# 24_PCIE-PCIE3_0_1x4Lanes_RC_64P.net
KiCad netlist of a schematic drawn in Altium Designer
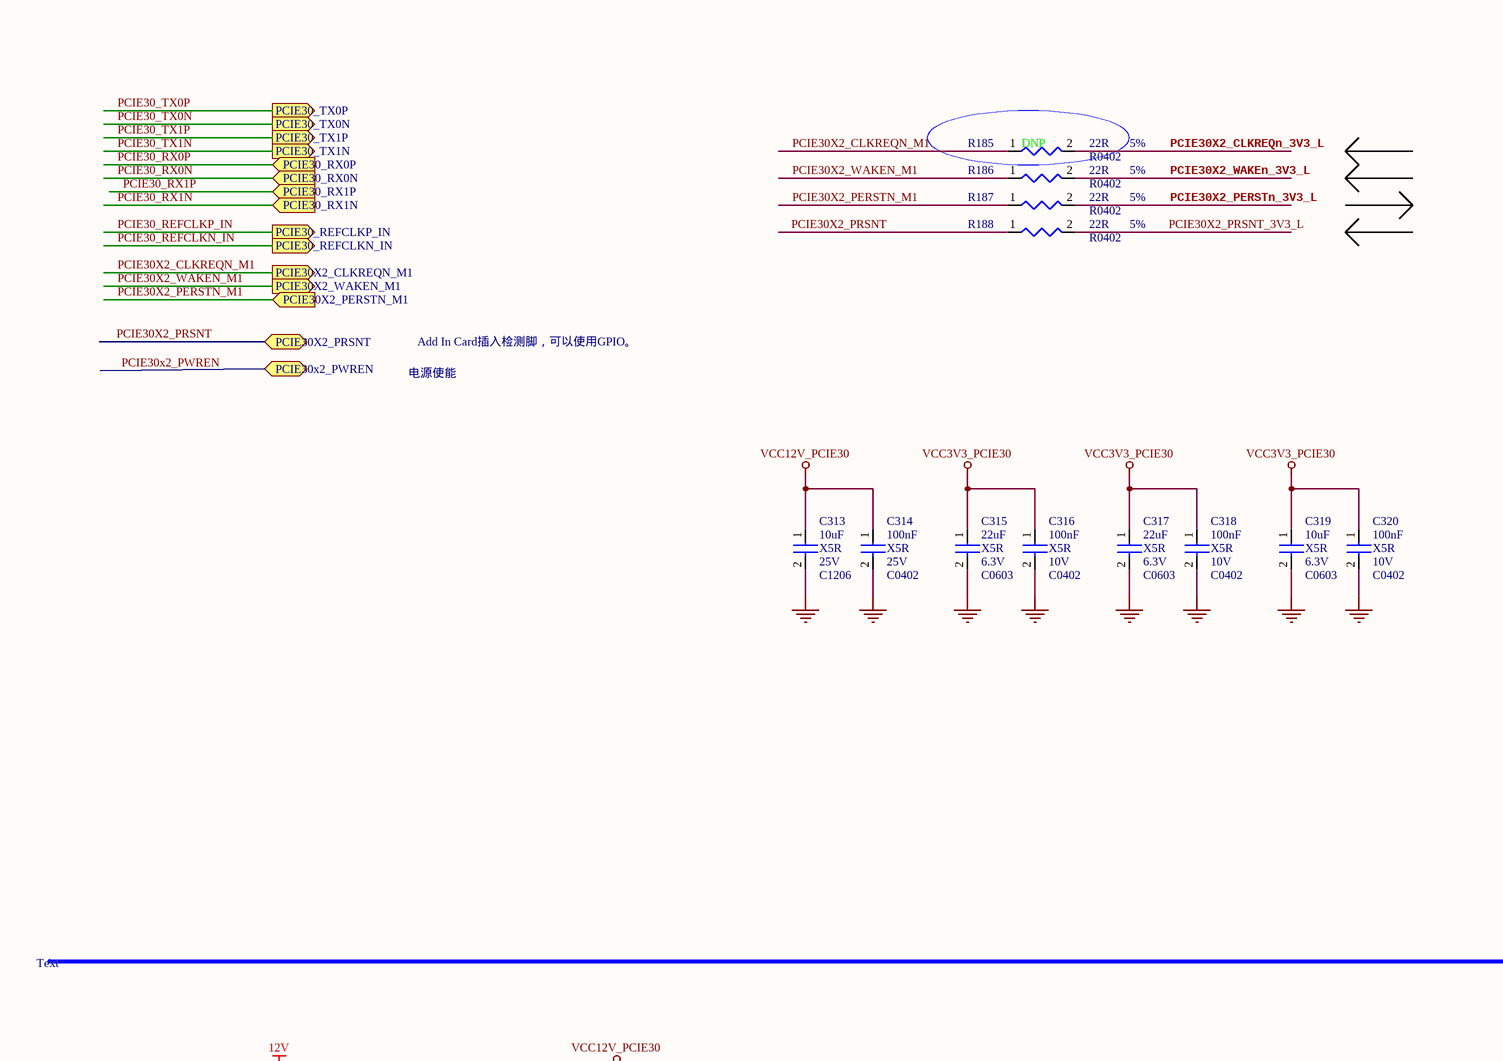
[diagram p0: 24_PCIE-PCIE3.0_1x4Lanes_RC_64P.SchDoc, top left]
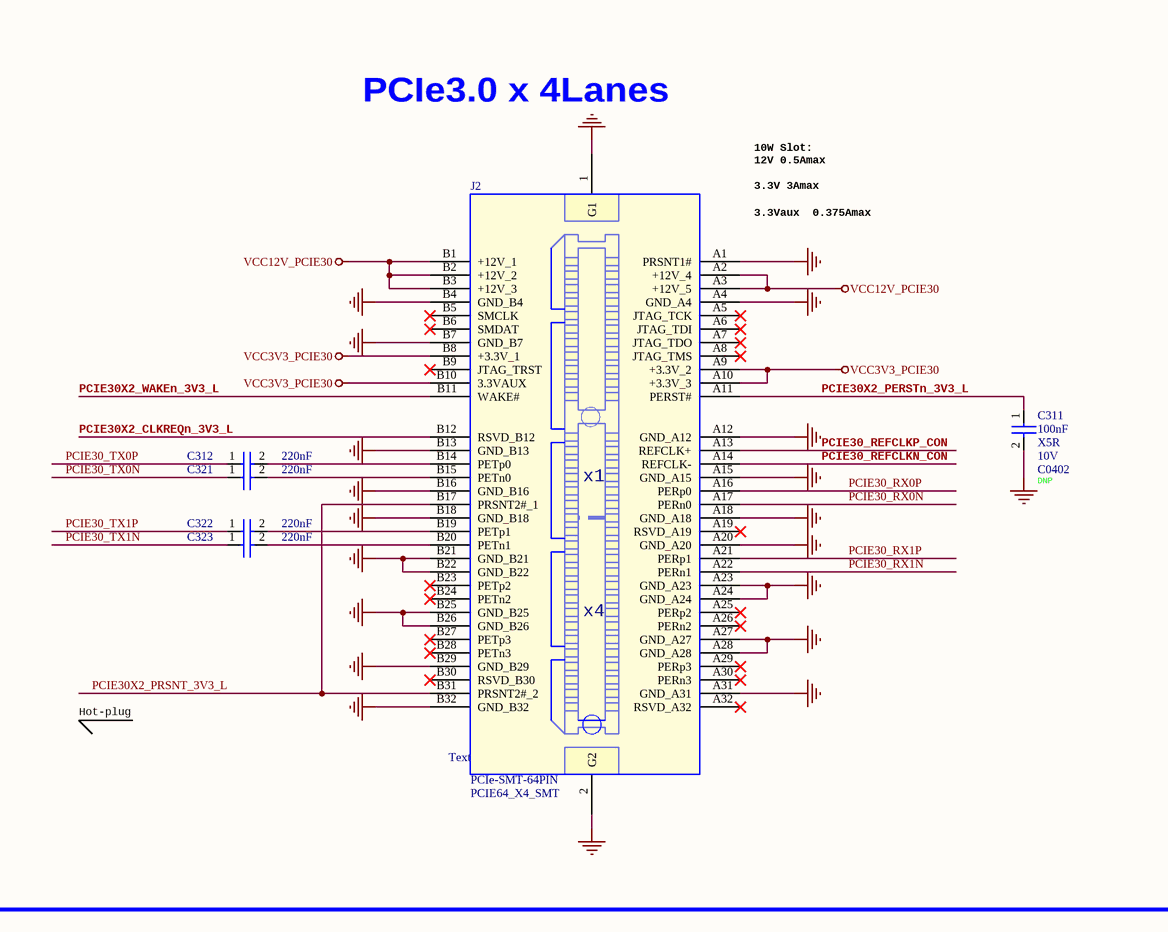
[diagram p1: 24_PCIE-PCIE3.0_1x4Lanes_RC_64P.SchDoc, top right]
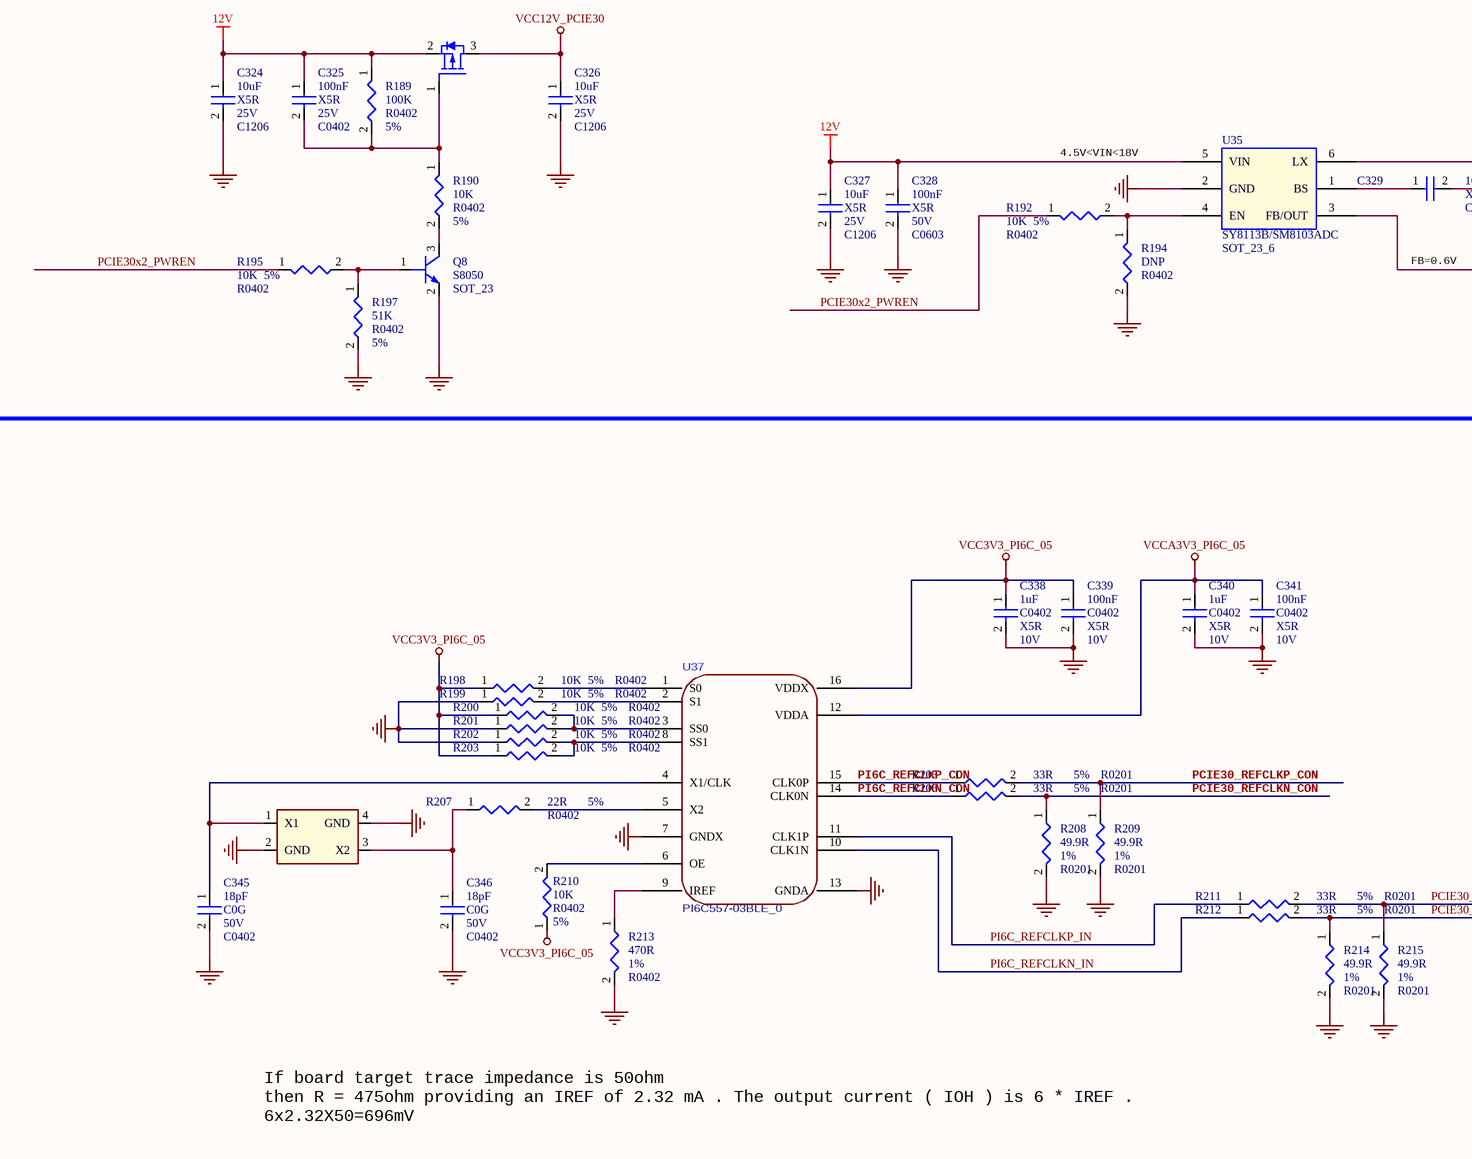
[diagram p2: 24_PCIE-PCIE3.0_1x4Lanes_RC_64P.SchDoc, bottom left]
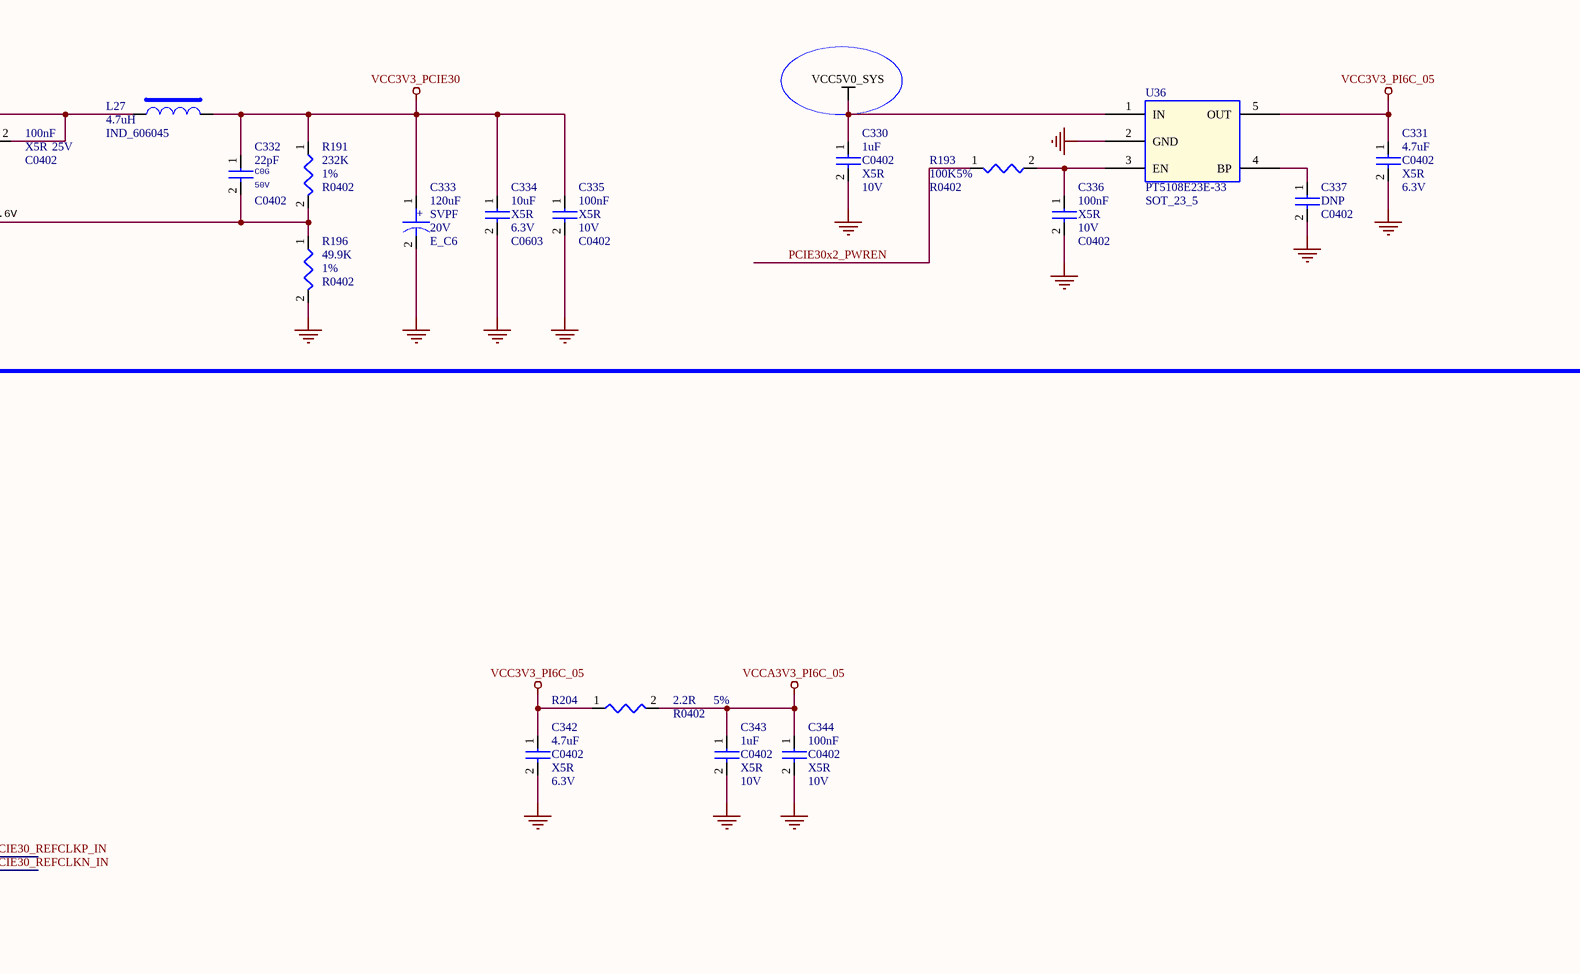
[diagram p3: 24_PCIE-PCIE3.0_1x4Lanes_RC_64P.SchDoc, bottom right]

(export (version "E")
  (design (tool "Eeschema 10.0.6"))
  (components
    (comp (ref "C311")
      (value "100nF")
      (footprint "C0402")
      (description "cap,100.00nF,+/-10%,10V,X5R,C0402")
      (fields
        (field (name "VOLTAGE") "10V")
        (field (name "PCB FOOTPRINT") "C0402")
        (field (name "DIELECTRIC") "X5R")
        (field (name "TOLERANCE") "10%")
        (field (name "MANUFACTURER") "TDK")
        (field (name "OPTION") "DNP")
        (field (name "CREATED BY") "JJJ")
      )
      (libsource (lib "*") (part "CAP NP"))
    )
    (comp (ref "C312")
      (value "220nF")
      (footprint "C0201")
      (description "cap,220.00nF,+/-10%,10V,X5R,C0201")
      (fields
        (field (name "MANUFACTURER") "TDK")
        (field (name "TOLERANCE") "10%")
        (field (name "CREATED BY") "JJJ")
      )
      (libsource (lib "*") (part "CAP NP"))
    )
    (comp (ref "C313")
      (value "10uF")
      (footprint "C1206")
      (description "cap,10.00uF,+/-10%,25V,X5R,C1206")
      (fields
        (field (name "VOLTAGE") "25V")
        (field (name "PCB FOOTPRINT") "C1206")
        (field (name "DIELECTRIC") "X5R")
        (field (name "MANUFACTURER") "TDK")
        (field (name "TOLERANCE") "10%")
        (field (name "CREATED BY") "JJJ")
      )
      (libsource (lib "*") (part "CAP NP"))
    )
    (comp (ref "C314")
      (value "100nF")
      (footprint "C0402")
      (description "cap,100.00nF,+/-10%,25V,X5R,C0402")
      (fields
        (field (name "VOLTAGE") "25V")
        (field (name "PCB FOOTPRINT") "C0402")
        (field (name "DIELECTRIC") "X5R")
        (field (name "TOLERANCE") "10%")
        (field (name "MANUFACTURER") "TDK")
        (field (name "CREATED BY") "JJJ")
      )
      (libsource (lib "*") (part "CAP NP"))
    )
    (comp (ref "C315")
      (value "22uF")
      (footprint "C0603")
      (description "cap,22.00uF,+/-20%,6.3V,X5R,C0603")
      (fields
        (field (name "VOLTAGE") "6.3V")
        (field (name "PCB FOOTPRINT") "C0603")
        (field (name "DIELECTRIC") "X5R")
        (field (name "MANUFACTURER") "TDK")
        (field (name "TOLERANCE") "20%")
        (field (name "CREATED BY") "JJJ")
      )
      (libsource (lib "*") (part "CAP NP"))
    )
    (comp (ref "C316")
      (value "100nF")
      (footprint "C0402")
      (description "cap,100.00nF,+/-10%,10V,X5R,C0402")
      (fields
        (field (name "VOLTAGE") "10V")
        (field (name "PCB FOOTPRINT") "C0402")
        (field (name "DIELECTRIC") "X5R")
        (field (name "MANUFACTURER") "TDK")
        (field (name "TOLERANCE") "10%")
        (field (name "CREATED BY") "JJJ")
      )
      (libsource (lib "*") (part "CAP NP"))
    )
    (comp (ref "C317")
      (value "22uF")
      (footprint "C0603")
      (description "cap,22.00uF,+/-20%,6.3V,X5R,C0603")
      (fields
        (field (name "VOLTAGE") "6.3V")
        (field (name "PCB FOOTPRINT") "C0603")
        (field (name "DIELECTRIC") "X5R")
        (field (name "MANUFACTURER") "TDK")
        (field (name "TOLERANCE") "20%")
        (field (name "CREATED BY") "JJJ")
      )
      (libsource (lib "*") (part "CAP NP"))
    )
    (comp (ref "C318")
      (value "100nF")
      (footprint "C0402")
      (description "cap,100.00nF,+/-10%,10V,X5R,C0402")
      (fields
        (field (name "VOLTAGE") "10V")
        (field (name "PCB FOOTPRINT") "C0402")
        (field (name "DIELECTRIC") "X5R")
        (field (name "MANUFACTURER") "TDK")
        (field (name "TOLERANCE") "10%")
        (field (name "CREATED BY") "JJJ")
      )
      (libsource (lib "*") (part "CAP NP"))
    )
    (comp (ref "C319")
      (value "10uF")
      (footprint "C0603")
      (description "cap,10.00uF,+/-10%,6.3V,X5R,C0603")
      (fields
        (field (name "VOLTAGE") "6.3V")
        (field (name "PCB FOOTPRINT") "C0603")
        (field (name "DIELECTRIC") "X5R")
        (field (name "TOLERANCE") "10%")
        (field (name "MANUFACTURER") "TDK")
        (field (name "CREATED BY") "JJJ")
      )
      (libsource (lib "*") (part "CAP NP"))
    )
    (comp (ref "C320")
      (value "100nF")
      (footprint "C0402")
      (description "cap,100.00nF,+/-10%,10V,X5R,C0402")
      (fields
        (field (name "VOLTAGE") "10V")
        (field (name "PCB FOOTPRINT") "C0402")
        (field (name "DIELECTRIC") "X5R")
        (field (name "TOLERANCE") "10%")
        (field (name "MANUFACTURER") "TDK")
        (field (name "CREATED BY") "JJJ")
      )
      (libsource (lib "*") (part "CAP NP"))
    )
    (comp (ref "C321")
      (value "220nF")
      (footprint "C0201")
      (description "cap,220.00nF,+/-10%,10V,X5R,C0201")
      (fields
        (field (name "MANUFACTURER") "TDK")
        (field (name "TOLERANCE") "10%")
        (field (name "CREATED BY") "JJJ")
      )
      (libsource (lib "*") (part "CAP NP"))
    )
    (comp (ref "C322")
      (value "220nF")
      (footprint "C0201")
      (description "cap,220.00nF,+/-10%,10V,X5R,C0201")
      (fields
        (field (name "MANUFACTURER") "TDK")
        (field (name "TOLERANCE") "10%")
        (field (name "CREATED BY") "JJJ")
      )
      (libsource (lib "*") (part "CAP NP"))
    )
    (comp (ref "C323")
      (value "220nF")
      (footprint "C0201")
      (description "cap,220.00nF,+/-10%,10V,X5R,C0201")
      (fields
        (field (name "MANUFACTURER") "TDK")
        (field (name "TOLERANCE") "10%")
        (field (name "CREATED BY") "JJJ")
      )
      (libsource (lib "*") (part "CAP NP"))
    )
    (comp (ref "C324")
      (value "10uF")
      (footprint "C1206")
      (description "cap,10.00uF,+/-10%,25V,X5R,C1206")
      (fields
        (field (name "VOLTAGE") "25V")
        (field (name "PCB FOOTPRINT") "C1206")
        (field (name "DIELECTRIC") "X5R")
        (field (name "TOLERANCE") "10%")
        (field (name "MANUFACTURER") "TDK")
        (field (name "CREATED BY") "JJJ")
      )
      (libsource (lib "*") (part "CAP NP"))
    )
    (comp (ref "C325")
      (value "100nF")
      (footprint "C0402")
      (description "cap,100.00nF,+/-10%,25V,X5R,C0402")
      (fields
        (field (name "VOLTAGE") "25V")
        (field (name "PCB FOOTPRINT") "C0402")
        (field (name "DIELECTRIC") "X5R")
        (field (name "MANUFACTURER") "TDK")
        (field (name "TOLERANCE") "10%")
        (field (name "CREATED BY") "JJJ")
      )
      (libsource (lib "*") (part "CAP NP"))
    )
    (comp (ref "C326")
      (value "10uF")
      (footprint "C1206")
      (description "cap,10.00uF,+/-10%,25V,X5R,C1206")
      (fields
        (field (name "VOLTAGE") "25V")
        (field (name "PCB FOOTPRINT") "C1206")
        (field (name "DIELECTRIC") "X5R")
        (field (name "TOLERANCE") "10%")
        (field (name "MANUFACTURER") "TDK")
        (field (name "CREATED BY") "JJJ")
      )
      (libsource (lib "*") (part "CAP NP"))
    )
    (comp (ref "C327")
      (value "10uF")
      (footprint "C1206")
      (description "cap,10.00uF,+/-10%,25V,X5R,C1206")
      (fields
        (field (name "VOLTAGE") "25V")
        (field (name "PCB FOOTPRINT") "C1206")
        (field (name "DIELECTRIC") "X5R")
        (field (name "MANUFACTURER") "TDK")
        (field (name "TOLERANCE") "10%")
        (field (name "CREATED BY") "JJJ")
      )
      (libsource (lib "*") (part "CAP NP"))
    )
    (comp (ref "C328")
      (value "100nF")
      (footprint "C0603")
      (description "cap,100.00nF,+/-10%,50V,X5R,C0603")
      (fields
        (field (name "VOLTAGE") "50V")
        (field (name "PCB FOOTPRINT") "C0603")
        (field (name "DIELECTRIC") "X5R")
        (field (name "MANUFACTURER") "TDK")
        (field (name "TOLERANCE") "10%")
        (field (name "CREATED BY") "JJJ")
      )
      (libsource (lib "*") (part "CAP NP"))
    )
    (comp (ref "C329")
      (value "100nF")
      (footprint "C0402")
      (description "cap,100.00nF,+/-10%,25V,X5R,C0402")
      (fields
        (field (name "VOLTAGE") "25V")
        (field (name "PCB FOOTPRINT") "C0402")
        (field (name "DIELECTRIC") "X5R")
        (field (name "TOLERANCE") "10%")
        (field (name "MANUFACTURER") "TDK")
        (field (name "CREATED BY") "JJJ")
      )
      (libsource (lib "*") (part "CAP NP"))
    )
    (comp (ref "C330")
      (value "1uF")
      (footprint "C0402")
      (description "cap,1.00uF,+/-10%,10V,X5R,C0402")
      (fields
        (field (name "VOLTAGE") "10V")
        (field (name "PCB FOOTPRINT") "C0402")
        (field (name "DIELECTRIC") "X5R")
        (field (name "TOLERANCE") "10%")
        (field (name "MANUFACTURER") "TDK")
        (field (name "CREATED BY") "JJJ")
      )
      (libsource (lib "*") (part "CAP NP"))
    )
    (comp (ref "C331")
      (value "4.7uF")
      (footprint "C0402")
      (description "cap,4.70uF,+/-10%,6.3V,X5R,C0402")
      (fields
        (field (name "VOLTAGE") "6.3V")
        (field (name "PCB FOOTPRINT") "C0402")
        (field (name "DIELECTRIC") "X5R")
        (field (name "MANUFACTURER") "TDK")
        (field (name "TOLERANCE") "10%")
        (field (name "CREATED BY") "JJJ")
      )
      (libsource (lib "*") (part "CAP NP"))
    )
    (comp (ref "C332")
      (value "22pF")
      (footprint "C0402")
      (description "cap,22.00pF,+/-5%,50V,C0G,C0402")
      (fields
        (field (name "VOLTAGE") "50V")
        (field (name "PCB FOOTPRINT") "C0402")
        (field (name "DIELECTRIC") "C0G")
        (field (name "TOLERANCE") "5%")
        (field (name "MANUFACTURER") "TDK")
        (field (name "CREATED BY") "JJJ")
      )
      (libsource (lib "*") (part "CAP NP"))
    )
    (comp (ref "C333")
      (value "120uF")
      (footprint "E_C6")
      (description "120uF,20V,25mR,SVPF")
      (fields
        (field (name "VOLTAGE") "20V")
        (field (name "DIELECTRIC") "SVPF")
        (field (name "PCB FOOTPRINT") "E_C6")
        (field (name "MANUFACTURER") "Panasonic")
        (field (name "TOLERANCE") "20%")
        (field (name "CREATED BY") "JJJ")
      )
      (libsource (lib "*") (part "CAP"))
    )
    (comp (ref "C334")
      (value "10uF")
      (footprint "C0603")
      (description "cap,10.00uF,+/-10%,6.3V,X5R,C0603")
      (fields
        (field (name "VOLTAGE") "6.3V")
        (field (name "PCB FOOTPRINT") "C0603")
        (field (name "DIELECTRIC") "X5R")
        (field (name "TOLERANCE") "10%")
        (field (name "MANUFACTURER") "TDK")
        (field (name "CREATED BY") "JJJ")
      )
      (libsource (lib "*") (part "CAP NP"))
    )
    (comp (ref "C335")
      (value "100nF")
      (footprint "C0402")
      (description "cap,100.00nF,+/-10%,10V,X5R,C0402")
      (fields
        (field (name "VOLTAGE") "10V")
        (field (name "PCB FOOTPRINT") "C0402")
        (field (name "DIELECTRIC") "X5R")
        (field (name "MANUFACTURER") "TDK")
        (field (name "TOLERANCE") "10%")
        (field (name "CREATED BY") "JJJ")
      )
      (libsource (lib "*") (part "CAP NP"))
    )
    (comp (ref "C336")
      (value "100nF")
      (footprint "C0402")
      (description "cap,100.00nF,+/-10%,10V,X5R,C0402")
      (fields
        (field (name "VOLTAGE") "10V")
        (field (name "PCB FOOTPRINT") "C0402")
        (field (name "DIELECTRIC") "X5R")
        (field (name "TOLERANCE") "10%")
        (field (name "MANUFACTURER") "TDK")
        (field (name "CREATED BY") "JJJ")
      )
      (libsource (lib "*") (part "CAP NP"))
    )
    (comp (ref "C337")
      (value "DNP")
      (footprint "C0402")
      (description "Did Not Place.")
      (fields (field (name "PCB FOOTPRINT") "C0402") (field (name "CREATED BY") "JJJ"))
      (libsource (lib "*") (part "CAP NP"))
    )
    (comp (ref "C338")
      (value "1uF")
      (footprint "C0402")
      (description "cap,1.00uF,+/-10%,10V,X5R,C0402")
      (fields
        (field (name "VOLTAGE") "10V")
        (field (name "PCB FOOTPRINT") "C0402")
        (field (name "DIELECTRIC") "X5R")
        (field (name "MANUFACTURER") "TDK")
        (field (name "TOLERANCE") "10%")
        (field (name "CREATED BY") "JJJ")
      )
      (libsource (lib "*") (part "CAP NP"))
    )
    (comp (ref "C339")
      (value "100nF")
      (footprint "C0402")
      (description "cap,100.00nF,+/-10%,10V,X5R,C0402")
      (fields
        (field (name "VOLTAGE") "10V")
        (field (name "PCB FOOTPRINT") "C0402")
        (field (name "DIELECTRIC") "X5R")
        (field (name "TOLERANCE") "10%")
        (field (name "MANUFACTURER") "TDK")
        (field (name "CREATED BY") "JJJ")
      )
      (libsource (lib "*") (part "CAP NP"))
    )
    (comp (ref "C340")
      (value "1uF")
      (footprint "C0402")
      (description "cap,1.00uF,+/-10%,10V,X5R,C0402")
      (fields
        (field (name "VOLTAGE") "10V")
        (field (name "PCB FOOTPRINT") "C0402")
        (field (name "DIELECTRIC") "X5R")
        (field (name "MANUFACTURER") "TDK")
        (field (name "TOLERANCE") "10%")
        (field (name "CREATED BY") "JJJ")
      )
      (libsource (lib "*") (part "CAP NP"))
    )
    (comp (ref "C341")
      (value "100nF")
      (footprint "C0402")
      (description "cap,100.00nF,+/-10%,10V,X5R,C0402")
      (fields
        (field (name "VOLTAGE") "10V")
        (field (name "PCB FOOTPRINT") "C0402")
        (field (name "DIELECTRIC") "X5R")
        (field (name "TOLERANCE") "10%")
        (field (name "MANUFACTURER") "TDK")
        (field (name "CREATED BY") "JJJ")
      )
      (libsource (lib "*") (part "CAP NP"))
    )
    (comp (ref "C342")
      (value "4.7uF")
      (footprint "C0402")
      (description "cap,4.70uF,+/-10%,6.3V,X5R,C0402")
      (fields
        (field (name "VOLTAGE") "6.3V")
        (field (name "PCB FOOTPRINT") "C0402")
        (field (name "DIELECTRIC") "X5R")
        (field (name "TOLERANCE") "10%")
        (field (name "MANUFACTURER") "TDK")
        (field (name "CREATED BY") "JJJ")
      )
      (libsource (lib "*") (part "CAP NP"))
    )
    (comp (ref "C343")
      (value "1uF")
      (footprint "C0402")
      (description "cap,1.00uF,+/-10%,10V,X5R,C0402")
      (fields
        (field (name "VOLTAGE") "10V")
        (field (name "PCB FOOTPRINT") "C0402")
        (field (name "DIELECTRIC") "X5R")
        (field (name "MANUFACTURER") "TDK")
        (field (name "TOLERANCE") "10%")
        (field (name "CREATED BY") "JJJ")
      )
      (libsource (lib "*") (part "CAP NP"))
    )
    (comp (ref "C344")
      (value "100nF")
      (footprint "C0402")
      (description "cap,100.00nF,+/-10%,10V,X5R,C0402")
      (fields
        (field (name "VOLTAGE") "10V")
        (field (name "PCB FOOTPRINT") "C0402")
        (field (name "DIELECTRIC") "X5R")
        (field (name "TOLERANCE") "10%")
        (field (name "MANUFACTURER") "TDK")
        (field (name "CREATED BY") "JJJ")
      )
      (libsource (lib "*") (part "CAP NP"))
    )
    (comp (ref "C345")
      (value "18pF")
      (footprint "C0402")
      (description "cap,18.00pF,+/-5%,50V,C0G,C0402")
      (fields
        (field (name "VOLTAGE") "50V")
        (field (name "PCB FOOTPRINT") "C0402")
        (field (name "DIELECTRIC") "C0G")
        (field (name "TOLERANCE") "5%")
        (field (name "MANUFACTURER") "TDK")
        (field (name "CREATED BY") "JJJ")
      )
      (libsource (lib "*") (part "CAP NP"))
    )
    (comp (ref "C346")
      (value "18pF")
      (footprint "C0402")
      (description "cap,18.00pF,+/-5%,50V,C0G,C0402")
      (fields
        (field (name "VOLTAGE") "50V")
        (field (name "PCB FOOTPRINT") "C0402")
        (field (name "DIELECTRIC") "C0G")
        (field (name "MANUFACTURER") "TDK")
        (field (name "TOLERANCE") "5%")
        (field (name "CREATED BY") "JJJ")
      )
      (libsource (lib "*") (part "CAP NP"))
    )
    (comp (ref "J2")
      (value "PCIe-SMT-64PIN")
      (footprint "PCIE64_X4_SMT")
      (fields (field (name "PCB FOOTPRINT") "PCIE64_X4_SMT"))
      (libsource (lib "*") (part "PCIeX4_1"))
    )
    (comp (ref "L27")
      (value "4.7uH")
      (footprint "IND_606045")
      (description "Power Inductor,4.7uH,0.2,IND_606045")
      (fields
        (field (name "PCB FOOTPRINT") "IND_606045")
        (field (name "MANUFACTURER") "sunlord")
        (field (name "TOLERANCE") "20%")
        (field (name "CREATED BY") "YWQ")
      )
      (libsource (lib "*") (part "INDUCTORS OF FERRITE_Dup1"))
    )
    (comp (ref "Q7") (value "MOSFET P") (footprint "SOT_23") (libsource (lib "RK3568核心板") (part "MOSFET P")))
    (comp (ref "Q8")
      (value "S8050")
      (footprint "SOT_23")
      (description "S8050,SOT23")
      (fields
        (field (name "PCB FOOTPRINT") "SOT_23")
        (field (name "MANUFACTURER") "长电")
        (field (name "CREATED BY") "JJJ")
      )
      (libsource (lib "*") (part "NPN"))
    )
    (comp (ref "R185")
      (value "22R")
      (footprint "R0402")
      (description "通用厚膜电阻,22R,+/-5%,R0402,1/16W.")
      (fields
        (field (name "PCB FOOTPRINT") "R0402")
        (field (name "TOLERANCE") "5%")
        (field (name "MANUFACTURER") "YAGEO")
        (field (name "OPTION") "DNP")
        (field (name "CREATED BY") "YTL")
      )
      (libsource (lib "*") (part "RESISTOR_Dup1"))
    )
    (comp (ref "R186")
      (value "22R")
      (footprint "R0402")
      (description "通用厚膜电阻,22R,+/-5%,R0402,1/16W.")
      (fields
        (field (name "PCB FOOTPRINT") "R0402")
        (field (name "TOLERANCE") "5%")
        (field (name "MANUFACTURER") "YAGEO")
        (field (name "CREATED BY") "YTL")
      )
      (libsource (lib "*") (part "RESISTOR_Dup1"))
    )
    (comp (ref "R187")
      (value "22R")
      (footprint "R0402")
      (description "通用厚膜电阻,22R,+/-5%,R0402,1/16W.")
      (fields
        (field (name "PCB FOOTPRINT") "R0402")
        (field (name "TOLERANCE") "5%")
        (field (name "MANUFACTURER") "YAGEO")
        (field (name "CREATED BY") "YTL")
      )
      (libsource (lib "*") (part "RESISTOR_Dup1"))
    )
    (comp (ref "R188")
      (value "22R")
      (footprint "R0402")
      (description "通用厚膜电阻,22R,+/-5%,R0402,1/16W.")
      (fields
        (field (name "PCB FOOTPRINT") "R0402")
        (field (name "TOLERANCE") "5%")
        (field (name "MANUFACTURER") "YAGEO")
        (field (name "CREATED BY") "YTL")
      )
      (libsource (lib "*") (part "RESISTOR_Dup1"))
    )
    (comp (ref "R189")
      (value "100K")
      (footprint "R0402")
      (description "通用厚膜电阻,100K,+/-5%,R0402,1/16W.")
      (fields
        (field (name "PCB FOOTPRINT") "R0402")
        (field (name "TOLERANCE") "5%")
        (field (name "MANUFACTURER") "YAGEO")
        (field (name "CREATED BY") "YTL")
      )
      (libsource (lib "*") (part "RESISTOR_Dup1"))
    )
    (comp (ref "R190")
      (value "10K")
      (footprint "R0402")
      (description "通用厚膜电阻,10K,+/-5%,R0402,1/16W.")
      (fields
        (field (name "PCB FOOTPRINT") "R0402")
        (field (name "TOLERANCE") "5%")
        (field (name "MANUFACTURER") "YAGEO")
        (field (name "CREATED BY") "YTL")
      )
      (libsource (lib "*") (part "RESISTOR_Dup1"))
    )
    (comp (ref "R191")
      (value "232K")
      (footprint "R0402")
      (description "通用厚膜电阻,232K,+/-1%,R0402,1/16W.")
      (fields
        (field (name "PCB FOOTPRINT") "R0402")
        (field (name "TOLERANCE") "1%")
        (field (name "MANUFACTURER") "YAGEO")
        (field (name "CREATED BY") "YTL")
      )
      (libsource (lib "*") (part "RESISTOR_Dup1"))
    )
    (comp (ref "R192")
      (value "10K")
      (footprint "R0402")
      (description "通用厚膜电阻,10K,+/-5%,R0402,1/16W.")
      (fields
        (field (name "PCB FOOTPRINT") "R0402")
        (field (name "TOLERANCE") "5%")
        (field (name "MANUFACTURER") "YAGEO")
        (field (name "CREATED BY") "YTL")
      )
      (libsource (lib "*") (part "RESISTOR_Dup1"))
    )
    (comp (ref "R193")
      (value "100K")
      (footprint "R0402")
      (description "通用厚膜电阻,100K,+/-5%,R0402,1/16W.")
      (fields
        (field (name "PCB FOOTPRINT") "R0402")
        (field (name "TOLERANCE") "5%")
        (field (name "MANUFACTURER") "YAGEO")
        (field (name "CREATED BY") "YTL")
      )
      (libsource (lib "*") (part "RESISTOR_Dup1"))
    )
    (comp (ref "R194")
      (value "DNP")
      (footprint "R0402")
      (description "Did Not Place.")
      (fields (field (name "PCB FOOTPRINT") "R0402") (field (name "CREATED BY") "JJJ"))
      (libsource (lib "*") (part "RESISTOR_Dup1"))
    )
    (comp (ref "R195")
      (value "10K")
      (footprint "R0402")
      (description "通用厚膜电阻,10K,+/-5%,R0402,1/16W.")
      (fields
        (field (name "PCB FOOTPRINT") "R0402")
        (field (name "TOLERANCE") "5%")
        (field (name "MANUFACTURER") "YAGEO")
        (field (name "CREATED BY") "YTL")
      )
      (libsource (lib "*") (part "RESISTOR_Dup1"))
    )
    (comp (ref "R196")
      (value "49.9K")
      (footprint "R0402")
      (description "通用厚膜电阻,49K9,+/-1%,R0402,1/16W.")
      (fields
        (field (name "PCB FOOTPRINT") "R0402")
        (field (name "TOLERANCE") "1%")
        (field (name "MANUFACTURER") "YAGEO")
        (field (name "CREATED BY") "YTL")
      )
      (libsource (lib "*") (part "RESISTOR_Dup1"))
    )
    (comp (ref "R197")
      (value "51K")
      (footprint "R0402")
      (description "通用厚膜电阻,51K,+/-5%,R0402,1/16W.")
      (fields
        (field (name "PCB FOOTPRINT") "R0402")
        (field (name "TOLERANCE") "5%")
        (field (name "MANUFACTURER") "YAGEO")
        (field (name "CREATED BY") "YTL")
      )
      (libsource (lib "*") (part "RESISTOR_Dup1"))
    )
    (comp (ref "R198")
      (value "10K")
      (footprint "R0402")
      (description "通用厚膜电阻,10K,+/-5%,R0402,1/16W.")
      (fields
        (field (name "PCB FOOTPRINT") "R0402")
        (field (name "TOLERANCE") "5%")
        (field (name "MANUFACTURER") "YAGEO")
        (field (name "CREATED BY") "YTL")
      )
      (libsource (lib "*") (part "RESISTOR_Dup1"))
    )
    (comp (ref "R199")
      (value "10K")
      (footprint "R0402")
      (description "通用厚膜电阻,10K,+/-5%,R0402,1/16W.")
      (fields
        (field (name "PCB FOOTPRINT") "R0402")
        (field (name "TOLERANCE") "5%")
        (field (name "MANUFACTURER") "YAGEO")
        (field (name "CREATED BY") "YTL")
      )
      (libsource (lib "*") (part "RESISTOR_Dup1"))
    )
    (comp (ref "R200")
      (value "10K")
      (footprint "R0402")
      (description "通用厚膜电阻,10K,+/-5%,R0402,1/16W.")
      (fields
        (field (name "PCB FOOTPRINT") "R0402")
        (field (name "TOLERANCE") "5%")
        (field (name "MANUFACTURER") "YAGEO")
        (field (name "CREATED BY") "YTL")
      )
      (libsource (lib "*") (part "RESISTOR_Dup1"))
    )
    (comp (ref "R201")
      (value "10K")
      (footprint "R0402")
      (description "通用厚膜电阻,10K,+/-5%,R0402,1/16W.")
      (fields
        (field (name "PCB FOOTPRINT") "R0402")
        (field (name "TOLERANCE") "5%")
        (field (name "MANUFACTURER") "YAGEO")
        (field (name "CREATED BY") "YTL")
      )
      (libsource (lib "*") (part "RESISTOR_Dup1"))
    )
    (comp (ref "R202")
      (value "10K")
      (footprint "R0402")
      (description "通用厚膜电阻,10K,+/-5%,R0402,1/16W.")
      (fields
        (field (name "PCB FOOTPRINT") "R0402")
        (field (name "TOLERANCE") "5%")
        (field (name "MANUFACTURER") "YAGEO")
        (field (name "CREATED BY") "YTL")
      )
      (libsource (lib "*") (part "RESISTOR_Dup1"))
    )
    (comp (ref "R203")
      (value "10K")
      (footprint "R0402")
      (description "通用厚膜电阻,10K,+/-5%,R0402,1/16W.")
      (fields
        (field (name "PCB FOOTPRINT") "R0402")
        (field (name "TOLERANCE") "5%")
        (field (name "MANUFACTURER") "YAGEO")
        (field (name "CREATED BY") "YTL")
      )
      (libsource (lib "*") (part "RESISTOR_Dup1"))
    )
    (comp (ref "R204")
      (value "2.2R")
      (footprint "R0402")
      (description "通用厚膜电阻,2R2,+/-5%,R0402,1/16W.")
      (fields
        (field (name "PCB FOOTPRINT") "R0402")
        (field (name "TOLERANCE") "5%")
        (field (name "MANUFACTURER") "YAGEO")
        (field (name "CREATED BY") "YTL")
      )
      (libsource (lib "*") (part "RESISTOR_Dup1"))
    )
    (comp (ref "R205")
      (value "33R")
      (footprint "R0402")
      (description "通用厚膜电阻,33R,+/-5%,R0201,1/20W.")
      (fields
        (field (name "PCB FOOTPRINT") "R0201")
        (field (name "TOLERANCE") "5%")
        (field (name "MANUFACTURER") "YAGEO")
        (field (name "CREATED BY") "YTL")
      )
      (libsource (lib "*") (part "RESISTOR_Dup1"))
    )
    (comp (ref "R206")
      (value "33R")
      (footprint "R0402")
      (description "通用厚膜电阻,33R,+/-5%,R0201,1/20W.")
      (fields
        (field (name "PCB FOOTPRINT") "R0201")
        (field (name "TOLERANCE") "5%")
        (field (name "MANUFACTURER") "YAGEO")
        (field (name "CREATED BY") "YTL")
      )
      (libsource (lib "*") (part "RESISTOR_Dup1"))
    )
    (comp (ref "R207")
      (value "22R")
      (footprint "R0402")
      (description "通用厚膜电阻,22R,+/-5%,R0402,1/16W.")
      (fields
        (field (name "PCB FOOTPRINT") "R0402")
        (field (name "TOLERANCE") "5%")
        (field (name "MANUFACTURER") "YAGEO")
        (field (name "CREATED BY") "YTL")
      )
      (libsource (lib "*") (part "RESISTOR_Dup1"))
    )
    (comp (ref "R208")
      (value "49.9R")
      (footprint "R0402")
      (description "通用厚膜电阻,49R9,+/-1%,R0201,1/20W.")
      (fields
        (field (name "PCB FOOTPRINT") "R0201")
        (field (name "TOLERANCE") "1%")
        (field (name "MANUFACTURER") "YAGEO")
        (field (name "CREATED BY") "YTL")
      )
      (libsource (lib "*") (part "RESISTOR_Dup1"))
    )
    (comp (ref "R209")
      (value "49.9R")
      (footprint "R0402")
      (description "通用厚膜电阻,49R9,+/-1%,R0201,1/20W.")
      (fields
        (field (name "PCB FOOTPRINT") "R0201")
        (field (name "TOLERANCE") "1%")
        (field (name "MANUFACTURER") "YAGEO")
        (field (name "CREATED BY") "YTL")
      )
      (libsource (lib "*") (part "RESISTOR_Dup1"))
    )
    (comp (ref "R210")
      (value "10K")
      (footprint "R0402")
      (description "通用厚膜电阻,10K,+/-5%,R0402,1/16W.")
      (fields
        (field (name "PCB FOOTPRINT") "R0402")
        (field (name "TOLERANCE") "5%")
        (field (name "MANUFACTURER") "YAGEO")
        (field (name "CREATED BY") "YTL")
      )
      (libsource (lib "*") (part "RESISTOR_Dup1"))
    )
    (comp (ref "R211")
      (value "33R")
      (footprint "R0402")
      (description "通用厚膜电阻,33R,+/-5%,R0201,1/20W.")
      (fields
        (field (name "PCB FOOTPRINT") "R0201")
        (field (name "TOLERANCE") "5%")
        (field (name "MANUFACTURER") "YAGEO")
        (field (name "CREATED BY") "YTL")
      )
      (libsource (lib "*") (part "RESISTOR_Dup1"))
    )
    (comp (ref "R212")
      (value "33R")
      (footprint "R0402")
      (description "通用厚膜电阻,33R,+/-5%,R0201,1/20W.")
      (fields
        (field (name "PCB FOOTPRINT") "R0201")
        (field (name "TOLERANCE") "5%")
        (field (name "MANUFACTURER") "YAGEO")
        (field (name "CREATED BY") "YTL")
      )
      (libsource (lib "*") (part "RESISTOR_Dup1"))
    )
    (comp (ref "R213")
      (value "470R")
      (footprint "R0402")
      (description "通用厚膜电阻,470R,+/-1%,R0402,1/16W.")
      (fields
        (field (name "PCB FOOTPRINT") "R0402")
        (field (name "TOLERANCE") "1%")
        (field (name "MANUFACTURER") "YAGEO")
        (field (name "CREATED BY") "YTL")
      )
      (libsource (lib "*") (part "RESISTOR_Dup1"))
    )
    (comp (ref "R214")
      (value "49.9R")
      (footprint "R0402")
      (description "通用厚膜电阻,49R9,+/-1%,R0201,1/20W.")
      (fields
        (field (name "PCB FOOTPRINT") "R0201")
        (field (name "TOLERANCE") "1%")
        (field (name "MANUFACTURER") "YAGEO")
        (field (name "CREATED BY") "YTL")
      )
      (libsource (lib "*") (part "RESISTOR_Dup1"))
    )
    (comp (ref "R215")
      (value "49.9R")
      (footprint "R0402")
      (description "通用厚膜电阻,49R9,+/-1%,R0201,1/20W.")
      (fields
        (field (name "PCB FOOTPRINT") "R0201")
        (field (name "TOLERANCE") "1%")
        (field (name "MANUFACTURER") "YAGEO")
        (field (name "CREATED BY") "YTL")
      )
      (libsource (lib "*") (part "RESISTOR_Dup1"))
    )
    (comp (ref "U35")
      (value "SY8113B/SM8103ADC")
      (footprint "SOT_23_6")
      (fields
        (field (name "PCB FOOTPRINT") "SOT_23_6")
        (field (name "MANUFACTURER") "Silergy（矽力杰）")
        (field (name "CREATED BY") "JJJ")
      )
      (libsource (lib "*") (part "DCDC_SY8113"))
    )
    (comp (ref "U36")
      (value "PT5108E23E-33")
      (footprint "SOT_23_5")
      (description "High-PSRR 600mA LDO.Output3.3V.")
      (fields
        (field (name "PCB FOOTPRINT") "SOT_23_5")
        (field (name "MANUFACTURER") "Powtech（华润矽威）")
        (field (name "CREATED BY") "JJJ")
      )
      (libsource (lib "*") (part "LDO_PT5108"))
    )
    (comp (ref "U37")
      (value "PI6C557-03BLE_0")
      (footprint "TSSOP-16_L5.0-W4.4-P0.65-LS6.4-BL")
      (libsource (lib "RK3568核心板") (part "PI6C557-03BLE_0"))
    )
    (comp (ref "Y3")
      (value "CRYSTAL_4P")
      (footprint "CRY4_3R20X2R50X0R80")
      (libsource (lib "RK3568核心板") (part "CRYSTAL_4P"))
    )
  )
  (nets
    (net (code "1") (name "/PCIE30X2_CLKREQN_M1") (class "Default")
      (node (ref "R185") (pin "1") (pinfunction "1_1") (pintype "passive"))
    )
    (net (code "2") (name "/PCIE30X2_CLKREQn_3V3_L") (class "Default")
      (node (ref "J2") (pin "B12") (pinfunction "RSVD_B12_B12") (pintype "passive"))
      (node (ref "R185") (pin "2") (pinfunction "2_2") (pintype "passive"))
    )
    (net (code "3") (name "/PCIE30X2_PERSTN_M1") (class "Default")
      (node (ref "R187") (pin "1") (pinfunction "1_1") (pintype "passive"))
    )
    (net (code "4") (name "/PCIE30X2_PERSTn_3V3_L") (class "Default")
      (node (ref "C311") (pin "1") (pinfunction "1_1") (pintype "passive"))
      (node (ref "J2") (pin "A11") (pinfunction "PERST#_A11") (pintype "passive"))
      (node (ref "R187") (pin "2") (pinfunction "2_2") (pintype "passive"))
    )
    (net (code "5") (name "/PCIE30X2_PRSNT") (class "Default")
      (node (ref "R188") (pin "1") (pinfunction "1_1") (pintype "passive"))
    )
    (net (code "6") (name "/PCIE30X2_PRSNT_3V3_L") (class "Default")
      (node (ref "J2") (pin "B17") (pinfunction "PRSNT2#_1_B17") (pintype "passive"))
      (node (ref "J2") (pin "B31") (pinfunction "PRSNT2#_2_B31") (pintype "passive"))
      (node (ref "R188") (pin "2") (pinfunction "2_2") (pintype "passive"))
    )
    (net (code "7") (name "/PCIE30X2_WAKEN_M1") (class "Default")
      (node (ref "R186") (pin "1") (pinfunction "1_1") (pintype "passive"))
    )
    (net (code "8") (name "/PCIE30X2_WAKEn_3V3_L") (class "Default")
      (node (ref "J2") (pin "B11") (pinfunction "WAKE#_B11") (pintype "passive"))
      (node (ref "R186") (pin "2") (pinfunction "2_2") (pintype "passive"))
    )
    (net (code "9") (name "/PCIE30_REFCLKN_CON") (class "Default")
      (node (ref "J2") (pin "A14") (pinfunction "REFCLK-_A14") (pintype "passive"))
      (node (ref "R206") (pin "2") (pinfunction "2_2") (pintype "passive"))
      (node (ref "R208") (pin "1") (pinfunction "1_1") (pintype "passive"))
    )
    (net (code "10") (name "/PCIE30_REFCLKN_IN") (class "Default")
      (node (ref "R212") (pin "2") (pinfunction "2_2") (pintype "passive"))
      (node (ref "R214") (pin "1") (pinfunction "1_1") (pintype "passive"))
    )
    (net (code "11") (name "/PCIE30_REFCLKP_CON") (class "Default")
      (node (ref "J2") (pin "A13") (pinfunction "REFCLK+_A13") (pintype "passive"))
      (node (ref "R205") (pin "2") (pinfunction "2_2") (pintype "passive"))
      (node (ref "R209") (pin "1") (pinfunction "1_1") (pintype "passive"))
    )
    (net (code "12") (name "/PCIE30_REFCLKP_IN") (class "Default")
      (node (ref "R211") (pin "2") (pinfunction "2_2") (pintype "passive"))
      (node (ref "R215") (pin "1") (pinfunction "1_1") (pintype "passive"))
    )
    (net (code "13") (name "/PCIE30_RX0N") (class "Default")
      (node (ref "J2") (pin "A17") (pinfunction "PERn0_A17") (pintype "passive"))
    )
    (net (code "14") (name "/PCIE30_RX0P") (class "Default")
      (node (ref "J2") (pin "A16") (pinfunction "PERp0_A16") (pintype "passive"))
    )
    (net (code "15") (name "/PCIE30_RX1N") (class "Default")
      (node (ref "J2") (pin "A22") (pinfunction "PERn1_A22") (pintype "passive"))
    )
    (net (code "16") (name "/PCIE30_RX1P") (class "Default")
      (node (ref "J2") (pin "A21") (pinfunction "PERp1_A21") (pintype "passive"))
    )
    (net (code "17") (name "/PCIE30_TX0N") (class "Default")
      (node (ref "C321") (pin "1") (pinfunction "1_1") (pintype "passive"))
    )
    (net (code "18") (name "/PCIE30_TX0P") (class "Default")
      (node (ref "C312") (pin "1") (pinfunction "1_1") (pintype "passive"))
    )
    (net (code "19") (name "/PCIE30_TX1N") (class "Default")
      (node (ref "C323") (pin "1") (pinfunction "1_1") (pintype "passive"))
    )
    (net (code "20") (name "/PCIE30_TX1P") (class "Default")
      (node (ref "C322") (pin "1") (pinfunction "1_1") (pintype "passive"))
    )
    (net (code "21") (name "/PCIE30x2_PWREN") (class "Default")
      (node (ref "R192") (pin "1") (pinfunction "1_1") (pintype "passive"))
      (node (ref "R193") (pin "1") (pinfunction "1_1") (pintype "passive"))
      (node (ref "R195") (pin "1") (pinfunction "1_1") (pintype "passive"))
    )
    (net (code "22") (name "/PI6C_REFCLKN_CON") (class "Default")
      (node (ref "R206") (pin "1") (pinfunction "1_1") (pintype "passive"))
      (node (ref "U37") (pin "14") (pinfunction "CLK0N_14") (pintype "passive"))
    )
    (net (code "23") (name "/PI6C_REFCLKN_IN") (class "Default")
      (node (ref "R212") (pin "1") (pinfunction "1_1") (pintype "passive"))
      (node (ref "U37") (pin "10") (pinfunction "CLK1N_10") (pintype "passive"))
    )
    (net (code "24") (name "/PI6C_REFCLKP_CON") (class "Default")
      (node (ref "R205") (pin "1") (pinfunction "1_1") (pintype "passive"))
      (node (ref "U37") (pin "15") (pinfunction "CLK0P_15") (pintype "passive"))
    )
    (net (code "25") (name "/PI6C_REFCLKP_IN") (class "Default")
      (node (ref "R211") (pin "1") (pinfunction "1_1") (pintype "passive"))
      (node (ref "U37") (pin "11") (pinfunction "CLK1P_11") (pintype "passive"))
    )
    (net (code "26") (name "12V") (class "Default")
      (node (ref "C324") (pin "1") (pinfunction "1_1") (pintype "passive"))
      (node (ref "C325") (pin "1") (pinfunction "1_1") (pintype "passive"))
      (node (ref "C327") (pin "1") (pinfunction "1_1") (pintype "passive"))
      (node (ref "C328") (pin "1") (pinfunction "1_1") (pintype "passive"))
      (node (ref "Q7") (pin "2") (pinfunction "SOURCE_2") (pintype "passive"))
      (node (ref "R189") (pin "1") (pinfunction "1_1") (pintype "passive"))
      (node (ref "U35") (pin "5") (pinfunction "VIN_5") (pintype "passive"))
    )
    (net (code "27") (name "GND") (class "Default")
      (node (ref "C311") (pin "2") (pinfunction "2_2") (pintype "passive"))
      (node (ref "C313") (pin "2") (pinfunction "2_2") (pintype "passive"))
      (node (ref "C314") (pin "2") (pinfunction "2_2") (pintype "passive"))
      (node (ref "C315") (pin "2") (pinfunction "2_2") (pintype "passive"))
      (node (ref "C316") (pin "2") (pinfunction "2_2") (pintype "passive"))
      (node (ref "C317") (pin "2") (pinfunction "2_2") (pintype "passive"))
      (node (ref "C318") (pin "2") (pinfunction "2_2") (pintype "passive"))
      (node (ref "C319") (pin "2") (pinfunction "2_2") (pintype "passive"))
      (node (ref "C320") (pin "2") (pinfunction "2_2") (pintype "passive"))
      (node (ref "C324") (pin "2") (pinfunction "2_2") (pintype "passive"))
      (node (ref "C326") (pin "2") (pinfunction "2_2") (pintype "passive"))
      (node (ref "C327") (pin "2") (pinfunction "2_2") (pintype "passive"))
      (node (ref "C328") (pin "2") (pinfunction "2_2") (pintype "passive"))
      (node (ref "C330") (pin "2") (pinfunction "2_2") (pintype "passive"))
      (node (ref "C331") (pin "2") (pinfunction "2_2") (pintype "passive"))
      (node (ref "C333") (pin "2") (pinfunction "2_2") (pintype "passive"))
      (node (ref "C334") (pin "2") (pinfunction "2_2") (pintype "passive"))
      (node (ref "C335") (pin "2") (pinfunction "2_2") (pintype "passive"))
      (node (ref "C336") (pin "2") (pinfunction "2_2") (pintype "passive"))
      (node (ref "C337") (pin "2") (pinfunction "2_2") (pintype "passive"))
      (node (ref "C338") (pin "2") (pinfunction "2_2") (pintype "passive"))
      (node (ref "C339") (pin "2") (pinfunction "2_2") (pintype "passive"))
      (node (ref "C340") (pin "2") (pinfunction "2_2") (pintype "passive"))
      (node (ref "C341") (pin "2") (pinfunction "2_2") (pintype "passive"))
      (node (ref "C342") (pin "2") (pinfunction "2_2") (pintype "passive"))
      (node (ref "C343") (pin "2") (pinfunction "2_2") (pintype "passive"))
      (node (ref "C344") (pin "2") (pinfunction "2_2") (pintype "passive"))
      (node (ref "C345") (pin "2") (pinfunction "2_2") (pintype "passive"))
      (node (ref "C346") (pin "2") (pinfunction "2_2") (pintype "passive"))
      (node (ref "J2") (pin "1") (pinfunction "G1_1") (pintype "passive"))
      (node (ref "J2") (pin "2") (pinfunction "G2_2") (pintype "passive"))
      (node (ref "J2") (pin "A1") (pinfunction "PRSNT1#_A1") (pintype "passive"))
      (node (ref "J2") (pin "A12") (pinfunction "GND_A12_A12") (pintype "passive"))
      (node (ref "J2") (pin "A15") (pinfunction "GND_A15_A15") (pintype "passive"))
      (node (ref "J2") (pin "A18") (pinfunction "GND_A18_A18") (pintype "passive"))
      (node (ref "J2") (pin "A20") (pinfunction "GND_A20_A20") (pintype "passive"))
      (node (ref "J2") (pin "A23") (pinfunction "GND_A23_A23") (pintype "passive"))
      (node (ref "J2") (pin "A24") (pinfunction "GND_A24_A24") (pintype "passive"))
      (node (ref "J2") (pin "A27") (pinfunction "GND_A27_A27") (pintype "passive"))
      (node (ref "J2") (pin "A28") (pinfunction "GND_A28_A28") (pintype "passive"))
      (node (ref "J2") (pin "A31") (pinfunction "GND_A31_A31") (pintype "passive"))
      (node (ref "J2") (pin "A4") (pinfunction "GND_A4_A4") (pintype "passive"))
      (node (ref "J2") (pin "B13") (pinfunction "GND_B13_B13") (pintype "passive"))
      (node (ref "J2") (pin "B16") (pinfunction "GND_B16_B16") (pintype "passive"))
      (node (ref "J2") (pin "B18") (pinfunction "GND_B18_B18") (pintype "passive"))
      (node (ref "J2") (pin "B21") (pinfunction "GND_B21_B21") (pintype "passive"))
      (node (ref "J2") (pin "B22") (pinfunction "GND_B22_B22") (pintype "passive"))
      (node (ref "J2") (pin "B25") (pinfunction "GND_B25_B25") (pintype "passive"))
      (node (ref "J2") (pin "B26") (pinfunction "GND_B26_B26") (pintype "passive"))
      (node (ref "J2") (pin "B29") (pinfunction "GND_B29_B29") (pintype "passive"))
      (node (ref "J2") (pin "B32") (pinfunction "GND_B32_B32") (pintype "passive"))
      (node (ref "J2") (pin "B4") (pinfunction "GND_B4_B4") (pintype "passive"))
      (node (ref "J2") (pin "B7") (pinfunction "GND_B7_B7") (pintype "passive"))
      (node (ref "Q8") (pin "2") (pinfunction "EMITTER_2") (pintype "passive"))
      (node (ref "R194") (pin "2") (pinfunction "2_2") (pintype "passive"))
      (node (ref "R196") (pin "2") (pinfunction "2_2") (pintype "passive"))
      (node (ref "R197") (pin "2") (pinfunction "2_2") (pintype "passive"))
      (node (ref "R199") (pin "1") (pinfunction "1_1") (pintype "passive"))
      (node (ref "R201") (pin "1") (pinfunction "1_1") (pintype "passive"))
      (node (ref "R202") (pin "1") (pinfunction "1_1") (pintype "passive"))
      (node (ref "R208") (pin "2") (pinfunction "2_2") (pintype "passive"))
      (node (ref "R209") (pin "2") (pinfunction "2_2") (pintype "passive"))
      (node (ref "R213") (pin "2") (pinfunction "2_2") (pintype "passive"))
      (node (ref "R214") (pin "2") (pinfunction "2_2") (pintype "passive"))
      (node (ref "R215") (pin "2") (pinfunction "2_2") (pintype "passive"))
      (node (ref "U35") (pin "2") (pinfunction "GND_2") (pintype "passive"))
      (node (ref "U36") (pin "2") (pinfunction "GND_2") (pintype "passive"))
      (node (ref "U37") (pin "13") (pinfunction "GNDA_13") (pintype "passive"))
      (node (ref "U37") (pin "7") (pinfunction "GNDX_7") (pintype "passive"))
      (node (ref "Y3") (pin "2") (pinfunction "GND_2") (pintype "power_in"))
      (node (ref "Y3") (pin "4") (pinfunction "GND_4") (pintype "power_in"))
    )
    (net (code "28") (name "Net-(J2-PETn0)") (class "Default")
      (node (ref "C321") (pin "2") (pinfunction "2_2") (pintype "passive"))
      (node (ref "J2") (pin "B15") (pinfunction "PETn0_B15") (pintype "passive"))
    )
    (net (code "29") (name "Net-(J2-PETn1)") (class "Default")
      (node (ref "C323") (pin "2") (pinfunction "2_2") (pintype "passive"))
      (node (ref "J2") (pin "B20") (pinfunction "PETn1_B20") (pintype "passive"))
    )
    (net (code "30") (name "Net-(J2-PETp0)") (class "Default")
      (node (ref "C312") (pin "2") (pinfunction "2_2") (pintype "passive"))
      (node (ref "J2") (pin "B14") (pinfunction "PETp0_B14") (pintype "passive"))
    )
    (net (code "31") (name "Net-(J2-PETp1)") (class "Default")
      (node (ref "C322") (pin "2") (pinfunction "2_2") (pintype "passive"))
      (node (ref "J2") (pin "B19") (pinfunction "PETp1_B19") (pintype "passive"))
    )
    (net (code "32") (name "Net-(Q7-GATE)") (class "Default")
      (node (ref "C325") (pin "2") (pinfunction "2_2") (pintype "passive"))
      (node (ref "Q7") (pin "1") (pinfunction "GATE_1") (pintype "passive"))
      (node (ref "R189") (pin "2") (pinfunction "2_2") (pintype "passive"))
      (node (ref "R190") (pin "1") (pinfunction "1_1") (pintype "passive"))
    )
    (net (code "33") (name "Net-(Q8-BASE)") (class "Default")
      (node (ref "Q8") (pin "1") (pinfunction "BASE_1") (pintype "passive"))
      (node (ref "R195") (pin "2") (pinfunction "2_2") (pintype "passive"))
      (node (ref "R197") (pin "1") (pinfunction "1_1") (pintype "passive"))
    )
    (net (code "34") (name "Net-(Q8-COLLECTOR)") (class "Default")
      (node (ref "Q8") (pin "3") (pinfunction "COLLECTOR_3") (pintype "passive"))
      (node (ref "R190") (pin "2") (pinfunction "2_2") (pintype "passive"))
    )
    (net (code "35") (name "Net-(U35-BS)") (class "Default")
      (node (ref "C329") (pin "1") (pinfunction "1_1") (pintype "passive"))
      (node (ref "U35") (pin "1") (pinfunction "BS_1") (pintype "passive"))
    )
    (net (code "36") (name "Net-(U35-EN)") (class "Default")
      (node (ref "R192") (pin "2") (pinfunction "2_2") (pintype "passive"))
      (node (ref "R194") (pin "1") (pinfunction "1_1") (pintype "passive"))
      (node (ref "U35") (pin "4") (pinfunction "EN_4") (pintype "passive"))
    )
    (net (code "37") (name "Net-(U35-FB{slash}OUT)") (class "Default")
      (node (ref "C332") (pin "2") (pinfunction "2_2") (pintype "passive"))
      (node (ref "R191") (pin "2") (pinfunction "2_2") (pintype "passive"))
      (node (ref "R196") (pin "1") (pinfunction "1_1") (pintype "passive"))
      (node (ref "U35") (pin "3") (pinfunction "FB/OUT_3") (pintype "passive"))
    )
    (net (code "38") (name "Net-(U35-LX)") (class "Default")
      (node (ref "C329") (pin "2") (pinfunction "2_2") (pintype "passive"))
      (node (ref "L27") (pin "1") (pinfunction "1_1") (pintype "passive"))
      (node (ref "U35") (pin "6") (pinfunction "LX_6") (pintype "passive"))
    )
    (net (code "39") (name "Net-(U36-BP)") (class "Default")
      (node (ref "C337") (pin "1") (pinfunction "1_1") (pintype "passive"))
      (node (ref "U36") (pin "4") (pinfunction "BP_4") (pintype "passive"))
    )
    (net (code "40") (name "Net-(U36-EN)") (class "Default")
      (node (ref "C336") (pin "1") (pinfunction "1_1") (pintype "passive"))
      (node (ref "R193") (pin "2") (pinfunction "2_2") (pintype "passive"))
      (node (ref "U36") (pin "3") (pinfunction "EN_3") (pintype "passive"))
    )
    (net (code "41") (name "Net-(U37-IREF)") (class "Default")
      (node (ref "R213") (pin "1") (pinfunction "1_1") (pintype "passive"))
      (node (ref "U37") (pin "9") (pinfunction "IREF_9") (pintype "passive"))
    )
    (net (code "42") (name "Net-(U37-OE)") (class "Default")
      (node (ref "R210") (pin "2") (pinfunction "2_2") (pintype "passive"))
      (node (ref "U37") (pin "6") (pinfunction "OE_6") (pintype "passive"))
    )
    (net (code "43") (name "Net-(U37-S0)") (class "Default")
      (node (ref "R198") (pin "2") (pinfunction "2_2") (pintype "passive"))
      (node (ref "U37") (pin "1") (pinfunction "S0_1") (pintype "passive"))
    )
    (net (code "44") (name "Net-(U37-S1)") (class "Default")
      (node (ref "R199") (pin "2") (pinfunction "2_2") (pintype "passive"))
      (node (ref "U37") (pin "2") (pinfunction "S1_2") (pintype "passive"))
    )
    (net (code "45") (name "Net-(U37-SS0)") (class "Default")
      (node (ref "R200") (pin "2") (pinfunction "2_2") (pintype "passive"))
      (node (ref "R201") (pin "2") (pinfunction "2_2") (pintype "passive"))
      (node (ref "U37") (pin "3") (pinfunction "SS0_3") (pintype "passive"))
    )
    (net (code "46") (name "Net-(U37-SS1)") (class "Default")
      (node (ref "R202") (pin "2") (pinfunction "2_2") (pintype "passive"))
      (node (ref "R203") (pin "2") (pinfunction "2_2") (pintype "passive"))
      (node (ref "U37") (pin "8") (pinfunction "SS1_8") (pintype "passive"))
    )
    (net (code "47") (name "Net-(U37-X1{slash}CLK)") (class "Default")
      (node (ref "C345") (pin "1") (pinfunction "1_1") (pintype "passive"))
      (node (ref "U37") (pin "4") (pinfunction "X1/CLK_4") (pintype "passive"))
      (node (ref "Y3") (pin "1") (pinfunction "X1_1") (pintype "passive"))
    )
    (net (code "48") (name "Net-(U37-X2)") (class "Default")
      (node (ref "R207") (pin "2") (pinfunction "2_2") (pintype "passive"))
      (node (ref "U37") (pin "5") (pinfunction "X2_5") (pintype "passive"))
    )
    (net (code "49") (name "Net-(Y3-X2)") (class "Default")
      (node (ref "C346") (pin "1") (pinfunction "1_1") (pintype "passive"))
      (node (ref "R207") (pin "1") (pinfunction "1_1") (pintype "passive"))
      (node (ref "Y3") (pin "3") (pinfunction "X2_3") (pintype "passive"))
    )
    (net (code "50") (name "VCC3V3_PCIE30") (class "Default")
      (node (ref "C315") (pin "1") (pinfunction "1_1") (pintype "passive"))
      (node (ref "C316") (pin "1") (pinfunction "1_1") (pintype "passive"))
      (node (ref "C317") (pin "1") (pinfunction "1_1") (pintype "passive"))
      (node (ref "C318") (pin "1") (pinfunction "1_1") (pintype "passive"))
      (node (ref "C319") (pin "1") (pinfunction "1_1") (pintype "passive"))
      (node (ref "C320") (pin "1") (pinfunction "1_1") (pintype "passive"))
      (node (ref "C332") (pin "1") (pinfunction "1_1") (pintype "passive"))
      (node (ref "C333") (pin "1") (pinfunction "1_1") (pintype "passive"))
      (node (ref "C334") (pin "1") (pinfunction "1_1") (pintype "passive"))
      (node (ref "C335") (pin "1") (pinfunction "1_1") (pintype "passive"))
      (node (ref "J2") (pin "A10") (pinfunction "+3.3V_3_A10") (pintype "passive"))
      (node (ref "J2") (pin "A9") (pinfunction "+3.3V_2_A9") (pintype "passive"))
      (node (ref "J2") (pin "B10") (pinfunction "3.3VAUX_B10") (pintype "passive"))
      (node (ref "J2") (pin "B8") (pinfunction "+3.3V_1_B8") (pintype "passive"))
      (node (ref "L27") (pin "2") (pinfunction "2_2") (pintype "passive"))
      (node (ref "R191") (pin "1") (pinfunction "1_1") (pintype "passive"))
    )
    (net (code "51") (name "VCC3V3_PI6C_05") (class "Default")
      (node (ref "C331") (pin "1") (pinfunction "1_1") (pintype "passive"))
      (node (ref "C338") (pin "1") (pinfunction "1_1") (pintype "passive"))
      (node (ref "C339") (pin "1") (pinfunction "1_1") (pintype "passive"))
      (node (ref "C342") (pin "1") (pinfunction "1_1") (pintype "passive"))
      (node (ref "R198") (pin "1") (pinfunction "1_1") (pintype "passive"))
      (node (ref "R200") (pin "1") (pinfunction "1_1") (pintype "passive"))
      (node (ref "R203") (pin "1") (pinfunction "1_1") (pintype "passive"))
      (node (ref "R204") (pin "1") (pinfunction "1_1") (pintype "passive"))
      (node (ref "R210") (pin "1") (pinfunction "1_1") (pintype "passive"))
      (node (ref "U36") (pin "5") (pinfunction "OUT_5") (pintype "passive"))
      (node (ref "U37") (pin "16") (pinfunction "VDDX_16") (pintype "passive"))
    )
    (net (code "52") (name "VCC5V0_SYS") (class "Default")
      (node (ref "C330") (pin "1") (pinfunction "1_1") (pintype "passive"))
      (node (ref "U36") (pin "1") (pinfunction "IN_1") (pintype "passive"))
    )
    (net (code "53") (name "VCC12V_PCIE30") (class "Default")
      (node (ref "C313") (pin "1") (pinfunction "1_1") (pintype "passive"))
      (node (ref "C314") (pin "1") (pinfunction "1_1") (pintype "passive"))
      (node (ref "C326") (pin "1") (pinfunction "1_1") (pintype "passive"))
      (node (ref "J2") (pin "A2") (pinfunction "+12V_4_A2") (pintype "passive"))
      (node (ref "J2") (pin "A3") (pinfunction "+12V_5_A3") (pintype "passive"))
      (node (ref "J2") (pin "B1") (pinfunction "+12V_1_B1") (pintype "passive"))
      (node (ref "J2") (pin "B2") (pinfunction "+12V_2_B2") (pintype "passive"))
      (node (ref "J2") (pin "B3") (pinfunction "+12V_3_B3") (pintype "passive"))
      (node (ref "Q7") (pin "3") (pinfunction "DRAIN_3") (pintype "passive"))
    )
    (net (code "54") (name "VCCA3V3_PI6C_05") (class "Default")
      (node (ref "C340") (pin "1") (pinfunction "1_1") (pintype "passive"))
      (node (ref "C341") (pin "1") (pinfunction "1_1") (pintype "passive"))
      (node (ref "C343") (pin "1") (pinfunction "1_1") (pintype "passive"))
      (node (ref "C344") (pin "1") (pinfunction "1_1") (pintype "passive"))
      (node (ref "R204") (pin "2") (pinfunction "2_2") (pintype "passive"))
      (node (ref "U37") (pin "12") (pinfunction "VDDA_12") (pintype "passive"))
    )
    (net (code "55") (name "unconnected-(J2-JTAG_TCK-PadA5)") (class "Default")
      (node (ref "J2") (pin "A5") (pinfunction "JTAG_TCK_A5") (pintype "passive+no_connect"))
    )
    (net (code "56") (name "unconnected-(J2-JTAG_TDI-PadA6)") (class "Default")
      (node (ref "J2") (pin "A6") (pinfunction "JTAG_TDI_A6") (pintype "passive+no_connect"))
    )
    (net (code "57") (name "unconnected-(J2-JTAG_TDO-PadA7)") (class "Default")
      (node (ref "J2") (pin "A7") (pinfunction "JTAG_TDO_A7") (pintype "passive+no_connect"))
    )
    (net (code "58") (name "unconnected-(J2-JTAG_TMS-PadA8)") (class "Default")
      (node (ref "J2") (pin "A8") (pinfunction "JTAG_TMS_A8") (pintype "passive+no_connect"))
    )
    (net (code "59") (name "unconnected-(J2-JTAG_TRST-PadB9)") (class "Default")
      (node (ref "J2") (pin "B9") (pinfunction "JTAG_TRST_B9") (pintype "passive+no_connect"))
    )
    (net (code "60") (name "unconnected-(J2-PERn2-PadA26)") (class "Default")
      (node (ref "J2") (pin "A26") (pinfunction "PERn2_A26") (pintype "passive+no_connect"))
    )
    (net (code "61") (name "unconnected-(J2-PERn3-PadA30)") (class "Default")
      (node (ref "J2") (pin "A30") (pinfunction "PERn3_A30") (pintype "passive+no_connect"))
    )
    (net (code "62") (name "unconnected-(J2-PERp2-PadA25)") (class "Default")
      (node (ref "J2") (pin "A25") (pinfunction "PERp2_A25") (pintype "passive+no_connect"))
    )
    (net (code "63") (name "unconnected-(J2-PERp3-PadA29)") (class "Default")
      (node (ref "J2") (pin "A29") (pinfunction "PERp3_A29") (pintype "passive+no_connect"))
    )
    (net (code "64") (name "unconnected-(J2-PETn2-PadB24)") (class "Default")
      (node (ref "J2") (pin "B24") (pinfunction "PETn2_B24") (pintype "passive+no_connect"))
    )
    (net (code "65") (name "unconnected-(J2-PETn3-PadB28)") (class "Default")
      (node (ref "J2") (pin "B28") (pinfunction "PETn3_B28") (pintype "passive+no_connect"))
    )
    (net (code "66") (name "unconnected-(J2-PETp2-PadB23)") (class "Default")
      (node (ref "J2") (pin "B23") (pinfunction "PETp2_B23") (pintype "passive+no_connect"))
    )
    (net (code "67") (name "unconnected-(J2-PETp3-PadB27)") (class "Default")
      (node (ref "J2") (pin "B27") (pinfunction "PETp3_B27") (pintype "passive+no_connect"))
    )
    (net (code "68") (name "unconnected-(J2-RSVD_A19-PadA19)") (class "Default")
      (node (ref "J2") (pin "A19") (pinfunction "RSVD_A19_A19") (pintype "passive+no_connect"))
    )
    (net (code "69") (name "unconnected-(J2-RSVD_A32-PadA32)") (class "Default")
      (node (ref "J2") (pin "A32") (pinfunction "RSVD_A32_A32") (pintype "passive+no_connect"))
    )
    (net (code "70") (name "unconnected-(J2-RSVD_B30-PadB30)") (class "Default")
      (node (ref "J2") (pin "B30") (pinfunction "RSVD_B30_B30") (pintype "passive+no_connect"))
    )
    (net (code "71") (name "unconnected-(J2-SMCLK-PadB5)") (class "Default")
      (node (ref "J2") (pin "B5") (pinfunction "SMCLK_B5") (pintype "passive+no_connect"))
    )
    (net (code "72") (name "unconnected-(J2-SMDAT-PadB6)") (class "Default")
      (node (ref "J2") (pin "B6") (pinfunction "SMDAT_B6") (pintype "passive+no_connect"))
    )
  )
)
